# Main.net
KiCad netlist of a schematic drawn in Altium Designer
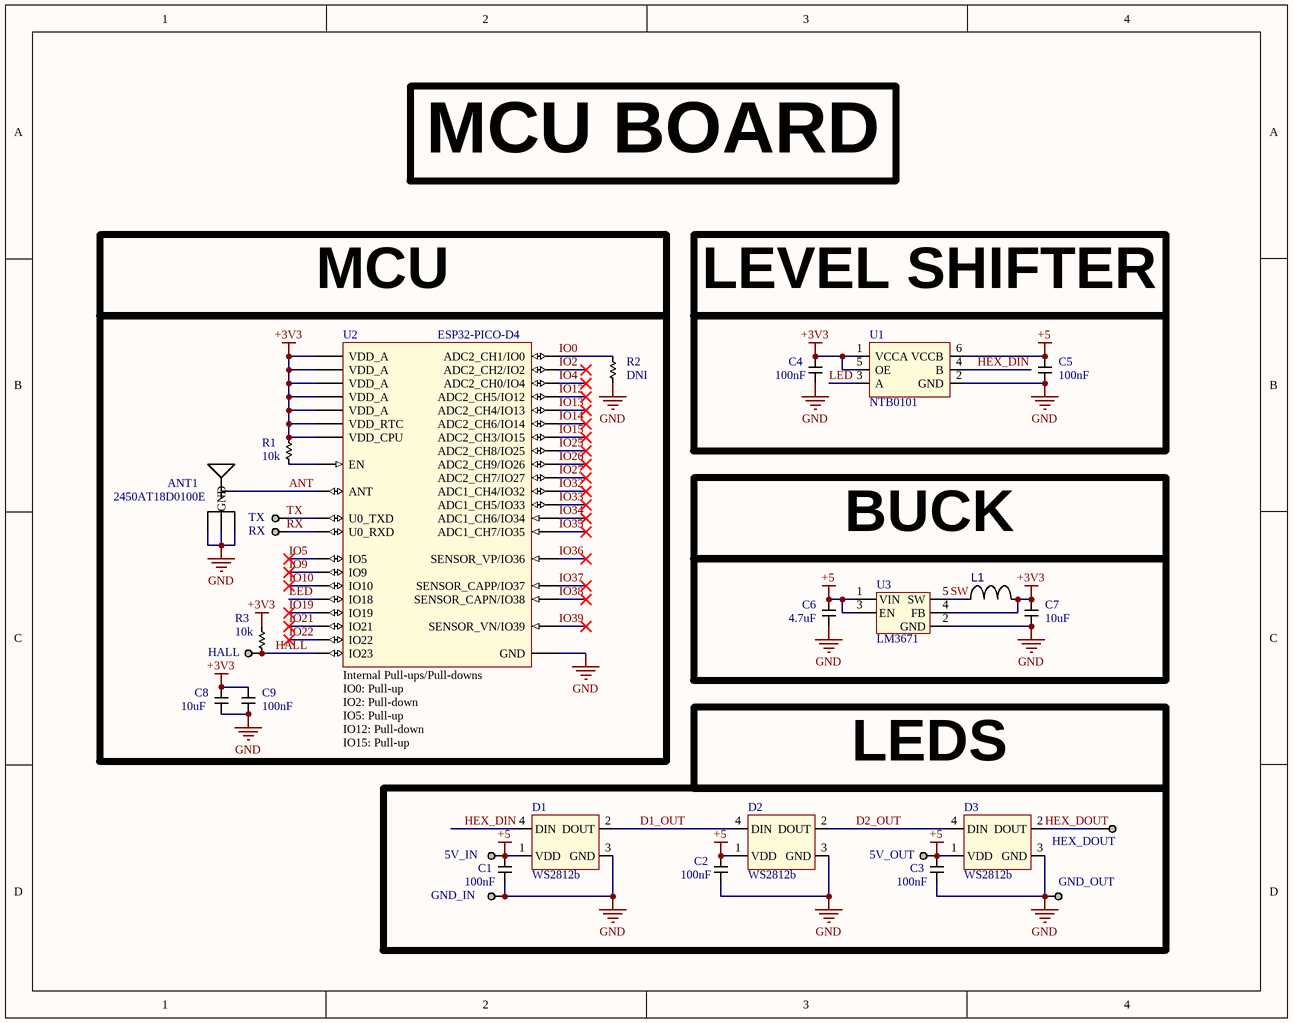
[diagram p0: Main.SchDoc]

(export (version "E")
  (design (tool "Eeschema 10.0.6"))
  (components
    (comp (ref "5V_IN")
      (value "18 AWG Hole")
      (footprint "18 AWG Hole")
      (libsource (lib "smLib") (part "18 AWG Hole"))
    )
    (comp (ref "5V_OUT")
      (value "18 AWG Hole")
      (footprint "18 AWG Hole")
      (libsource (lib "smLib") (part "18 AWG Hole"))
    )
    (comp (ref "ANT1")
      (value "2450AT18D0100E")
      (footprint "2450AT18D0100E")
      (description "2450AT18D0100E 2.4GHz  Chip RF Antenna 2.4GHz ~ 2.5GHz 1.5dBi Solder Surface Mount")
      (libsource (lib "smLib") (part "2450AT18D0100E"))
    )
    (comp (ref "C1")
      (value "100nF")
      (footprint "CAP_0805_HIGH")
      (description "0805 Capacitor")
      (libsource (lib "smLib") (part "Capacitor_0805"))
    )
    (comp (ref "C2")
      (value "100nF")
      (footprint "CAP_0805_HIGH")
      (description "0805 Capacitor")
      (libsource (lib "smLib") (part "Capacitor_0805"))
    )
    (comp (ref "C3")
      (value "100nF")
      (footprint "CAP_0805_HIGH")
      (description "0805 Capacitor")
      (libsource (lib "smLib") (part "Capacitor_0805"))
    )
    (comp (ref "C4")
      (value "100nF")
      (footprint "CAP_0402_HIGH")
      (description "0402 Capacitor")
      (libsource (lib "smLib") (part "Capacitor_0402"))
    )
    (comp (ref "C5")
      (value "100nF")
      (footprint "CAP_0402_HIGH")
      (description "0402 Capacitor")
      (libsource (lib "smLib") (part "Capacitor_0402"))
    )
    (comp (ref "C6")
      (value "4.7uF")
      (footprint "CAP_0603_HIGH")
      (description "0603 Capacitor")
      (libsource (lib "smLib") (part "Capacitor_0603"))
    )
    (comp (ref "C7")
      (value "10uF")
      (footprint "CAP_0603_HIGH")
      (description "0603 Capacitor")
      (libsource (lib "smLib") (part "Capacitor_0603"))
    )
    (comp (ref "C8")
      (value "10uF")
      (footprint "CAP_0603_HIGH")
      (description "0603 Capacitor")
      (libsource (lib "smLib") (part "Capacitor_0603"))
    )
    (comp (ref "C9")
      (value "100nF")
      (footprint "CAP_0402_HIGH")
      (description "0402 Capacitor")
      (libsource (lib "smLib") (part "Capacitor_0402"))
    )
    (comp (ref "D1")
      (value "WS2812b")
      (footprint "WS2812b")
      (description "WS2812b LED RGB")
      (libsource (lib "smLib") (part "WS2812b"))
    )
    (comp (ref "D2")
      (value "WS2812b")
      (footprint "WS2812b")
      (description "WS2812b LED RGB")
      (libsource (lib "smLib") (part "WS2812b"))
    )
    (comp (ref "D3")
      (value "WS2812b")
      (footprint "WS2812b")
      (description "WS2812b LED RGB")
      (libsource (lib "smLib") (part "WS2812b"))
    )
    (comp (ref "GND_IN")
      (value "18 AWG Hole")
      (footprint "18 AWG Hole")
      (libsource (lib "smLib") (part "18 AWG Hole"))
    )
    (comp (ref "GND_OUT")
      (value "18 AWG Hole")
      (footprint "18 AWG Hole")
      (libsource (lib "smLib") (part "18 AWG Hole"))
    )
    (comp (ref "HALL")
      (value "18 AWG Hole")
      (footprint "18 AWG Hole")
      (libsource (lib "smLib") (part "18 AWG Hole"))
    )
    (comp (ref "HEX_DOUT")
      (value "18 AWG Hole")
      (footprint "18 AWG Hole")
      (libsource (lib "smLib") (part "18 AWG Hole"))
    )
    (comp (ref "L1")
      (value "CIGT201610EH2R2MNE")
      (footprint "CIGT201610EH2R2MNE")
      (description "CIGT201610EH2R2MNE 2.2µH Unshielded Thin Film Inductor 2.5A 87mOhm Max 0806 (2016 Metric)")
      (libsource (lib "smLib") (part "CIGT201610EH2R2MNE"))
    )
    (comp (ref "R1")
      (value "10k")
      (footprint "RES_0402_HIGH")
      (description "0402 Resistor")
      (libsource (lib "smLib") (part "Resistor_0402"))
    )
    (comp (ref "R2")
      (value "DNI")
      (footprint "RES_0805_HIGH")
      (description "0805 Resistor")
      (libsource (lib "smLib") (part "Resistor_0805"))
    )
    (comp (ref "R3")
      (value "10k")
      (footprint "RES_0402_HIGH")
      (description "0402 Resistor")
      (libsource (lib "smLib") (part "Resistor_0402"))
    )
    (comp (ref "RX")
      (value "0.1\" Header")
      (footprint "0.1\" Header")
      (libsource (lib "smLib") (part "0.1{dblquote} Header"))
    )
    (comp (ref "TX")
      (value "0.1\" Header")
      (footprint "0.1\" Header")
      (libsource (lib "smLib") (part "0.1{dblquote} Header"))
    )
    (comp (ref "U1")
      (value "NTB0101")
      (footprint "NTB0101")
      (description "NTB0101  Voltage Level Translator Bidirectional 1 Circuit 1 Channel 100Mbps")
      (libsource (lib "smLib") (part "NTB0101"))
    )
    (comp (ref "U2")
      (value "ESP32-PICO-D4")
      (footprint "ESP32-PICO-D4")
      (description "ESP32-PICO-D4 SoC")
      (libsource (lib "smLib") (part "ESP32-PICO-D4"))
    )
    (comp (ref "U3")
      (value "LM3671")
      (footprint "LM3671-BGA")
      (description "LM3671 IC REG BUCK 3.3V 0.6A SYNC 5USMD")
      (libsource (lib "smLib") (part "LM3671"))
    )
  )
  (nets
    (net (code "1") (name "+3V3") (class "Default")
      (node (ref "C4") (pin "2") (pinfunction "2_2") (pintype "passive"))
      (node (ref "C7") (pin "2") (pinfunction "2_2") (pintype "passive"))
      (node (ref "C8") (pin "2") (pinfunction "2_2") (pintype "passive"))
      (node (ref "C9") (pin "2") (pinfunction "2_2") (pintype "passive"))
      (node (ref "L1") (pin "2") (pinfunction "2_2") (pintype "passive"))
      (node (ref "R1") (pin "2") (pinfunction "2_2") (pintype "passive"))
      (node (ref "R3") (pin "2") (pinfunction "2_2") (pintype "passive"))
      (node (ref "U1") (pin "1") (pinfunction "VCCA_1") (pintype "passive"))
      (node (ref "U1") (pin "5") (pinfunction "OE_5") (pintype "passive"))
      (node (ref "U2") (pin "1") (pinfunction "VDD_A_1") (pintype "power_in"))
      (node (ref "U2") (pin "19") (pinfunction "VDD_RTC_19") (pintype "power_in"))
      (node (ref "U2") (pin "3") (pinfunction "VDD_A_3") (pintype "power_in"))
      (node (ref "U2") (pin "37") (pinfunction "VDD_CPU_37") (pintype "power_in"))
      (node (ref "U2") (pin "4") (pinfunction "VDD_A_4") (pintype "power_in"))
      (node (ref "U2") (pin "43") (pinfunction "VDD_A_43") (pintype "power_in"))
      (node (ref "U2") (pin "46") (pinfunction "VDD_A_46") (pintype "power_in"))
      (node (ref "U3") (pin "4") (pinfunction "FB_4") (pintype "passive"))
    )
    (net (code "2") (name "+5") (class "Default")
      (node (ref "5V_IN") (pin "1") (pinfunction "1_1") (pintype "passive"))
      (node (ref "5V_OUT") (pin "1") (pinfunction "1_1") (pintype "passive"))
      (node (ref "C1") (pin "2") (pinfunction "2_2") (pintype "passive"))
      (node (ref "C2") (pin "2") (pinfunction "2_2") (pintype "passive"))
      (node (ref "C3") (pin "2") (pinfunction "2_2") (pintype "passive"))
      (node (ref "C5") (pin "2") (pinfunction "2_2") (pintype "passive"))
      (node (ref "C6") (pin "2") (pinfunction "2_2") (pintype "passive"))
      (node (ref "D1") (pin "1") (pinfunction "VDD_1") (pintype "passive"))
      (node (ref "D2") (pin "1") (pinfunction "VDD_1") (pintype "passive"))
      (node (ref "D3") (pin "1") (pinfunction "VDD_1") (pintype "passive"))
      (node (ref "U1") (pin "6") (pinfunction "VCCB_6") (pintype "passive"))
      (node (ref "U3") (pin "1") (pinfunction "VIN_1") (pintype "passive"))
      (node (ref "U3") (pin "3") (pinfunction "EN_3") (pintype "passive"))
    )
    (net (code "3") (name "/ANT") (class "Default")
      (node (ref "ANT1") (pin "1") (pinfunction "FEED_1") (pintype "passive"))
      (node (ref "U2") (pin "2") (pinfunction "ANT_2") (pintype "bidirectional"))
    )
    (net (code "4") (name "/D1_OUT") (class "Default")
      (node (ref "D1") (pin "2") (pinfunction "DOUT_2") (pintype "passive"))
      (node (ref "D2") (pin "4") (pinfunction "DIN_4") (pintype "passive"))
    )
    (net (code "5") (name "/D2_OUT") (class "Default")
      (node (ref "D2") (pin "2") (pinfunction "DOUT_2") (pintype "passive"))
      (node (ref "D3") (pin "4") (pinfunction "DIN_4") (pintype "passive"))
    )
    (net (code "6") (name "/HALL") (class "Default")
      (node (ref "HALL") (pin "1") (pinfunction "1_1") (pintype "passive"))
      (node (ref "R3") (pin "1") (pinfunction "1_1") (pintype "passive"))
      (node (ref "U2") (pin "36") (pinfunction "IO23_36") (pintype "bidirectional"))
    )
    (net (code "7") (name "/HEX_DIN") (class "Default")
      (node (ref "D1") (pin "4") (pinfunction "DIN_4") (pintype "passive"))
      (node (ref "U1") (pin "4") (pinfunction "B_4") (pintype "passive"))
    )
    (net (code "8") (name "/HEX_DOUT") (class "Default")
      (node (ref "D3") (pin "2") (pinfunction "DOUT_2") (pintype "passive"))
      (node (ref "HEX_DOUT") (pin "1") (pinfunction "1_1") (pintype "passive"))
    )
    (net (code "9") (name "/IO0") (class "Default")
      (node (ref "R2") (pin "2") (pinfunction "2_2") (pintype "passive"))
      (node (ref "U2") (pin "23") (pinfunction "ADC2_CH1/IO0_23") (pintype "bidirectional"))
    )
    (net (code "10") (name "/IO2") (class "Default")
      (node (ref "U2") (pin "22") (pinfunction "ADC2_CH2/IO2_22") (pintype "bidirectional+no_connect"))
    )
    (net (code "11") (name "/IO4") (class "Default")
      (node (ref "U2") (pin "24") (pinfunction "ADC2_CH0/IO4_24") (pintype "bidirectional+no_connect"))
    )
    (net (code "12") (name "/IO5") (class "Default")
      (node (ref "U2") (pin "34") (pinfunction "IO5_34") (pintype "bidirectional+no_connect"))
    )
    (net (code "13") (name "/IO9") (class "Default")
      (node (ref "U2") (pin "28") (pinfunction "IO9_28") (pintype "bidirectional+no_connect"))
    )
    (net (code "14") (name "/IO10") (class "Default")
      (node (ref "U2") (pin "29") (pinfunction "IO10_29") (pintype "bidirectional+no_connect"))
    )
    (net (code "15") (name "/IO12") (class "Default")
      (node (ref "U2") (pin "18") (pinfunction "ADC2_CH5/IO12_18") (pintype "bidirectional+no_connect"))
    )
    (net (code "16") (name "/IO13") (class "Default")
      (node (ref "U2") (pin "20") (pinfunction "ADC2_CH4/IO13_20") (pintype "bidirectional+no_connect"))
    )
    (net (code "17") (name "/IO14") (class "Default")
      (node (ref "U2") (pin "17") (pinfunction "ADC2_CH6/IO14_17") (pintype "bidirectional+no_connect"))
    )
    (net (code "18") (name "/IO15") (class "Default")
      (node (ref "U2") (pin "21") (pinfunction "ADC2_CH3/IO15_21") (pintype "bidirectional+no_connect"))
    )
    (net (code "19") (name "/IO19") (class "Default")
      (node (ref "U2") (pin "38") (pinfunction "IO19_38") (pintype "bidirectional+no_connect"))
    )
    (net (code "20") (name "/IO21") (class "Default")
      (node (ref "U2") (pin "42") (pinfunction "IO21_42") (pintype "bidirectional+no_connect"))
    )
    (net (code "21") (name "/IO22") (class "Default")
      (node (ref "U2") (pin "39") (pinfunction "IO22_39") (pintype "bidirectional+no_connect"))
    )
    (net (code "22") (name "/IO25") (class "Default")
      (node (ref "U2") (pin "14") (pinfunction "ADC2_CH8/IO25_14") (pintype "bidirectional+no_connect"))
    )
    (net (code "23") (name "/IO26") (class "Default")
      (node (ref "U2") (pin "15") (pinfunction "ADC2_CH9/IO26_15") (pintype "bidirectional+no_connect"))
    )
    (net (code "24") (name "/IO27") (class "Default")
      (node (ref "U2") (pin "16") (pinfunction "ADC2_CH7/IO27_16") (pintype "bidirectional+no_connect"))
    )
    (net (code "25") (name "/IO32") (class "Default")
      (node (ref "U2") (pin "12") (pinfunction "ADC1_CH4/IO32_12") (pintype "bidirectional+no_connect"))
    )
    (net (code "26") (name "/IO33") (class "Default")
      (node (ref "U2") (pin "13") (pinfunction "ADC1_CH5/IO33_13") (pintype "bidirectional+no_connect"))
    )
    (net (code "27") (name "/IO34") (class "Default")
      (node (ref "U2") (pin "10") (pinfunction "ADC1_CH6/IO34_10") (pintype "input+no_connect"))
    )
    (net (code "28") (name "/IO35") (class "Default")
      (node (ref "U2") (pin "11") (pinfunction "ADC1_CH7/IO35_11") (pintype "input+no_connect"))
    )
    (net (code "29") (name "/IO36") (class "Default")
      (node (ref "U2") (pin "5") (pinfunction "SENSOR_VP/IO36_5") (pintype "input+no_connect"))
    )
    (net (code "30") (name "/IO37") (class "Default")
      (node (ref "U2") (pin "6") (pinfunction "SENSOR_CAPP/IO37_6") (pintype "input+no_connect"))
    )
    (net (code "31") (name "/IO38") (class "Default")
      (node (ref "U2") (pin "7") (pinfunction "SENSOR_CAPN/IO38_7") (pintype "input+no_connect"))
    )
    (net (code "32") (name "/IO39") (class "Default")
      (node (ref "U2") (pin "8") (pinfunction "SENSOR_VN/IO39_8") (pintype "input+no_connect"))
    )
    (net (code "33") (name "/LED") (class "Default")
      (node (ref "U1") (pin "3") (pinfunction "A_3") (pintype "passive"))
      (node (ref "U2") (pin "35") (pinfunction "IO18_35") (pintype "bidirectional"))
    )
    (net (code "35") (name "/SW") (class "Default")
      (node (ref "L1") (pin "1") (pinfunction "1_1") (pintype "passive"))
      (node (ref "U3") (pin "5") (pinfunction "SW_5") (pintype "passive"))
    )
    (net (code "37") (name "GND") (class "Default")
      (node (ref "ANT1") (pin "2") (pinfunction "GND_2") (pintype "passive"))
      (node (ref "ANT1") (pin "3") (pinfunction "GND_3") (pintype "passive"))
      (node (ref "ANT1") (pin "4") (pinfunction "GND_4") (pintype "passive"))
      (node (ref "C1") (pin "1") (pinfunction "1_1") (pintype "passive"))
      (node (ref "C2") (pin "1") (pinfunction "1_1") (pintype "passive"))
      (node (ref "C3") (pin "1") (pinfunction "1_1") (pintype "passive"))
      (node (ref "C4") (pin "1") (pinfunction "1_1") (pintype "passive"))
      (node (ref "C5") (pin "1") (pinfunction "1_1") (pintype "passive"))
      (node (ref "C6") (pin "1") (pinfunction "1_1") (pintype "passive"))
      (node (ref "C7") (pin "1") (pinfunction "1_1") (pintype "passive"))
      (node (ref "C8") (pin "1") (pinfunction "1_1") (pintype "passive"))
      (node (ref "C9") (pin "1") (pinfunction "1_1") (pintype "passive"))
      (node (ref "D1") (pin "3") (pinfunction "GND_3") (pintype "passive"))
      (node (ref "D2") (pin "3") (pinfunction "GND_3") (pintype "passive"))
      (node (ref "D3") (pin "3") (pinfunction "GND_3") (pintype "passive"))
      (node (ref "GND_IN") (pin "1") (pinfunction "1_1") (pintype "passive"))
      (node (ref "GND_OUT") (pin "1") (pinfunction "1_1") (pintype "passive"))
      (node (ref "R2") (pin "1") (pinfunction "1_1") (pintype "passive"))
      (node (ref "U1") (pin "2") (pinfunction "GND_2") (pintype "passive"))
      (node (ref "U2") (pin "49") (pinfunction "GND_49") (pintype "power_in"))
      (node (ref "U3") (pin "2") (pinfunction "GND_2") (pintype "passive"))
    )
    (net (code "38") (name "Net-(U2-EN)") (class "Default")
      (node (ref "R1") (pin "1") (pinfunction "1_1") (pintype "passive"))
      (node (ref "U2") (pin "9") (pinfunction "EN_9") (pintype "input"))
    )
    (net (code "39") (name "Net-(U2-U0_RXD)") (class "Default")
      (node (ref "RX") (pin "1") (pinfunction "1_1") (pintype "passive"))
      (node (ref "U2") (pin "40") (pinfunction "U0_RXD_40") (pintype "bidirectional"))
    )
    (net (code "40") (name "Net-(U2-U0_TXD)") (class "Default")
      (node (ref "TX") (pin "1") (pinfunction "1_1") (pintype "passive"))
      (node (ref "U2") (pin "41") (pinfunction "U0_TXD_41") (pintype "bidirectional"))
    )
  )
)
